# EDC-1.net
KiCad netlist of a schematic drawn in EAGLE
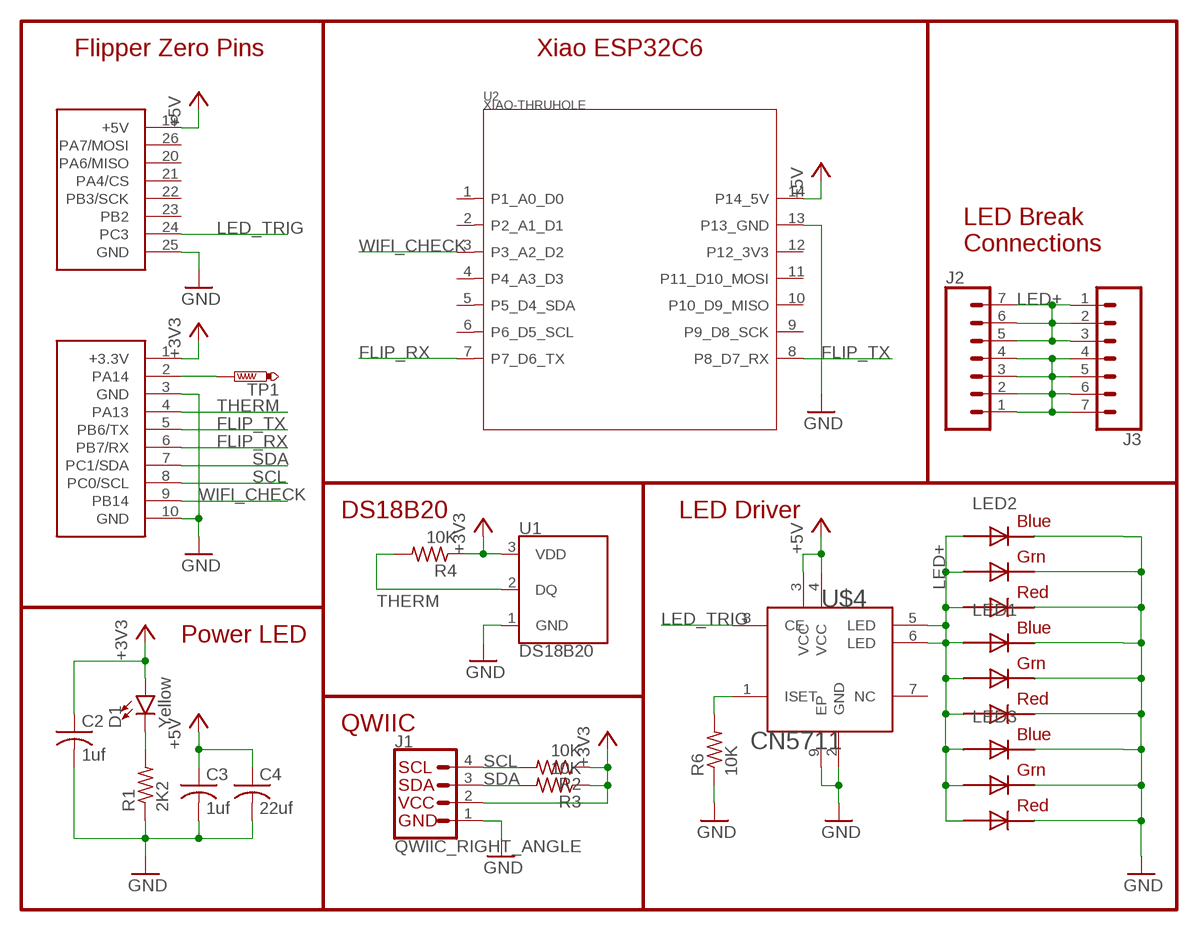
[diagram p0: schematic, sheet 1]

(export (version "E")
  (design (tool "Eeschema 10.0.6"))
  (components
    (comp (ref "C2")
      (value "1uf")
      (footprint "eagle-import:C0805")
      (libsource (lib "eagle-import") (part "C-USC0805"))
    )
    (comp (ref "C3")
      (value "1uf")
      (footprint "eagle-import:C0805")
      (libsource (lib "eagle-import") (part "C-USC0805"))
    )
    (comp (ref "C4")
      (value "22uf")
      (footprint "eagle-import:C3216")
      (libsource (lib "eagle-import") (part "C-USC3216"))
    )
    (comp (ref "D1")
      (value "Yellow")
      (footprint "eagle-import:LED-1206")
      (libsource (lib "eagle-import") (part "LED-YELLOWLILYPAD"))
    )
    (comp (ref "J1")
      (value "QWIIC_RIGHT_ANGLE")
      (footprint "eagle-import:JST04_1MM_RA")
      (libsource (lib "eagle-import") (part "QWIIC_CONNECTORJS-1MM"))
    )
    (comp (ref "J2")
      (value "CONN_07LONGPADS")
      (footprint "eagle-import:1X07_LONGPADS")
      (libsource (lib "eagle-import") (part "CONN_07LONGPADS"))
    )
    (comp (ref "J3")
      (value "CONN_07LONGPADS")
      (footprint "eagle-import:1X07_LONGPADS")
      (libsource (lib "eagle-import") (part "CONN_07LONGPADS"))
    )
    (comp (ref "LED1")
      (value "RGBLED5050")
      (footprint "eagle-import:RGBLED5050")
      (libsource (lib "eagle-import") (part "RGBLED5050"))
    )
    (comp (ref "LED2")
      (value "RGBLED5050")
      (footprint "eagle-import:RGBLED5050")
      (libsource (lib "eagle-import") (part "RGBLED5050"))
    )
    (comp (ref "LED3")
      (value "RGBLED5050")
      (footprint "eagle-import:RGBLED5050")
      (libsource (lib "eagle-import") (part "RGBLED5050"))
    )
    (comp (ref "R1")
      (value "2K2")
      (footprint "eagle-import:R0805")
      (libsource (lib "eagle-import") (part "R-US_R0805"))
    )
    (comp (ref "R2")
      (value "10K")
      (footprint "eagle-import:R0805")
      (libsource (lib "eagle-import") (part "R-US_R0805"))
    )
    (comp (ref "R3")
      (value "10K")
      (footprint "eagle-import:R0805")
      (libsource (lib "eagle-import") (part "R-US_R0805"))
    )
    (comp (ref "R4")
      (value "10K")
      (footprint "eagle-import:R0805")
      (libsource (lib "eagle-import") (part "R-US_R0805"))
    )
    (comp (ref "R6")
      (value "10K")
      (footprint "eagle-import:R0805")
      (libsource (lib "eagle-import") (part "R-US_R0805"))
    )
    (comp (ref "TP1")
      (value "PTR1PAD1-13")
      (footprint "eagle-import:P1-13")
      (libsource (lib "eagle-import") (part "PTR1PAD1-13"))
    )
    (comp (ref "U$1")
      (value "BOTH-SMD")
      (footprint "eagle-import:BOTH-SMD")
      (libsource (lib "eagle-import") (part "BOTH-SMD"))
    )
    (comp (ref "U$4")
      (value "CN5711")
      (footprint "eagle-import:SOIC127P600X175-9N")
      (libsource (lib "eagle-import") (part "CN5711"))
    )
    (comp (ref "U1")
      (value "DS18B20")
      (footprint "eagle-import:TO-92-AMMO")
      (fields (field (name "MF") "UMW"))
      (libsource (lib "eagle-import") (part "DS18B20"))
    )
    (comp (ref "U2")
      (value "XIAO-THRUHOLE")
      (footprint "eagle-import:XIAO-GENERIC-THRUHOLE-MODULE14P-2.54-21X17.8MM")
      (libsource (lib "eagle-import") (part "XIAO-THRUHOLE"))
    )
  )
  (nets
    (net (code "1") (name "+3V3") (class "Default")
      (node (ref "C2") (pin "1") (pinfunction "1_1") (pintype "passive"))
      (node (ref "D1") (pin "A") (pinfunction "A_A") (pintype "passive"))
      (node (ref "J1") (pin "2") (pinfunction "2_2") (pintype "power_in"))
      (node (ref "R2") (pin "1") (pinfunction "1_1") (pintype "passive"))
      (node (ref "R3") (pin "1") (pinfunction "1_1") (pintype "passive"))
      (node (ref "R4") (pin "1") (pinfunction "1_1") (pintype "passive"))
      (node (ref "U$1") (pin "1") (pinfunction "+3.3V_1") (pintype "bidirectional"))
      (node (ref "U1") (pin "3") (pinfunction "VDD_3") (pintype "power_in"))
    )
    (net (code "2") (name "+5V") (class "Default")
      (node (ref "C3") (pin "1") (pinfunction "1_1") (pintype "passive"))
      (node (ref "C4") (pin "1") (pinfunction "1_1") (pintype "passive"))
      (node (ref "U$1") (pin "19") (pinfunction "+5V_19") (pintype "bidirectional"))
      (node (ref "U$4") (pin "3") (pinfunction "VCC_3") (pintype "bidirectional"))
      (node (ref "U$4") (pin "4") (pinfunction "VCC_4") (pintype "bidirectional"))
      (node (ref "U2") (pin "14") (pinfunction "P14_5V_14") (pintype "bidirectional"))
    )
    (net (code "3") (name "/FLIP_RX") (class "Default")
      (node (ref "U$1") (pin "6") (pinfunction "PB7/RX_6") (pintype "bidirectional"))
      (node (ref "U2") (pin "7") (pinfunction "P7_D6_TX_7") (pintype "bidirectional"))
    )
    (net (code "4") (name "/FLIP_TX") (class "Default")
      (node (ref "U$1") (pin "5") (pinfunction "PB6/TX_5") (pintype "bidirectional"))
      (node (ref "U2") (pin "8") (pinfunction "P8_D7_RX_8") (pintype "bidirectional"))
    )
    (net (code "5") (name "/LED+") (class "Default")
      (node (ref "J2") (pin "5") (pinfunction "5_5") (pintype "passive"))
      (node (ref "J2") (pin "6") (pinfunction "6_6") (pintype "passive"))
      (node (ref "J2") (pin "7") (pinfunction "7_7") (pintype "passive"))
      (node (ref "J3") (pin "1") (pinfunction "1_1") (pintype "passive"))
      (node (ref "J3") (pin "2") (pinfunction "2_2") (pintype "passive"))
      (node (ref "J3") (pin "3") (pinfunction "3_3") (pintype "passive"))
      (node (ref "LED1") (pin "1") (pinfunction "GREEN_A_1") (pintype "bidirectional"))
      (node (ref "LED1") (pin "2") (pinfunction "RED_A_2") (pintype "bidirectional"))
      (node (ref "LED1") (pin "3") (pinfunction "BLUE_A_3") (pintype "bidirectional"))
      (node (ref "LED2") (pin "1") (pinfunction "GREEN_A_1") (pintype "bidirectional"))
      (node (ref "LED2") (pin "2") (pinfunction "RED_A_2") (pintype "bidirectional"))
      (node (ref "LED2") (pin "3") (pinfunction "BLUE_A_3") (pintype "bidirectional"))
      (node (ref "LED3") (pin "1") (pinfunction "GREEN_A_1") (pintype "bidirectional"))
      (node (ref "LED3") (pin "2") (pinfunction "RED_A_2") (pintype "bidirectional"))
      (node (ref "LED3") (pin "3") (pinfunction "BLUE_A_3") (pintype "bidirectional"))
      (node (ref "U$4") (pin "5") (pinfunction "LED_5") (pintype "bidirectional"))
      (node (ref "U$4") (pin "6") (pinfunction "LED_6") (pintype "bidirectional"))
    )
    (net (code "6") (name "/LED_TRIG") (class "Default")
      (node (ref "U$1") (pin "24") (pinfunction "PC3_24") (pintype "bidirectional"))
      (node (ref "U$4") (pin "8") (pinfunction "CE_8") (pintype "bidirectional"))
    )
    (net (code "7") (name "/SCL") (class "Default")
      (node (ref "J1") (pin "4") (pinfunction "4_4") (pintype "passive"))
      (node (ref "R2") (pin "2") (pinfunction "2_2") (pintype "passive"))
      (node (ref "U$1") (pin "8") (pinfunction "PC0/SCL_8") (pintype "bidirectional"))
    )
    (net (code "8") (name "/SDA") (class "Default")
      (node (ref "J1") (pin "3") (pinfunction "3_3") (pintype "passive"))
      (node (ref "R3") (pin "2") (pinfunction "2_2") (pintype "passive"))
      (node (ref "U$1") (pin "7") (pinfunction "PC1/SDA_7") (pintype "bidirectional"))
    )
    (net (code "9") (name "/THERM") (class "Default")
      (node (ref "R4") (pin "2") (pinfunction "2_2") (pintype "passive"))
      (node (ref "U$1") (pin "4") (pinfunction "PA13_4") (pintype "bidirectional"))
      (node (ref "U1") (pin "2") (pinfunction "DQ_2") (pintype "bidirectional"))
    )
    (net (code "10") (name "/WIFI_CHECK") (class "Default")
      (node (ref "U$1") (pin "9") (pinfunction "PB14_9") (pintype "bidirectional"))
      (node (ref "U2") (pin "3") (pinfunction "P3_A2_D2_3") (pintype "bidirectional"))
    )
    (net (code "11") (name "GND") (class "Default")
      (node (ref "C2") (pin "2") (pinfunction "2_2") (pintype "passive"))
      (node (ref "C3") (pin "2") (pinfunction "2_2") (pintype "passive"))
      (node (ref "C4") (pin "2") (pinfunction "2_2") (pintype "passive"))
      (node (ref "J1") (pin "1") (pinfunction "1_1") (pintype "power_in"))
      (node (ref "J2") (pin "1") (pinfunction "1_1") (pintype "passive"))
      (node (ref "J2") (pin "2") (pinfunction "2_2") (pintype "passive"))
      (node (ref "J2") (pin "3") (pinfunction "3_3") (pintype "passive"))
      (node (ref "J2") (pin "4") (pinfunction "4_4") (pintype "passive"))
      (node (ref "J3") (pin "4") (pinfunction "4_4") (pintype "passive"))
      (node (ref "J3") (pin "5") (pinfunction "5_5") (pintype "passive"))
      (node (ref "J3") (pin "6") (pinfunction "6_6") (pintype "passive"))
      (node (ref "J3") (pin "7") (pinfunction "7_7") (pintype "passive"))
      (node (ref "LED1") (pin "4") (pinfunction "BLUE_C_4") (pintype "bidirectional"))
      (node (ref "LED1") (pin "5") (pinfunction "RED_C_5") (pintype "bidirectional"))
      (node (ref "LED1") (pin "6") (pinfunction "GREEN_C_6") (pintype "bidirectional"))
      (node (ref "LED2") (pin "4") (pinfunction "BLUE_C_4") (pintype "bidirectional"))
      (node (ref "LED2") (pin "5") (pinfunction "RED_C_5") (pintype "bidirectional"))
      (node (ref "LED2") (pin "6") (pinfunction "GREEN_C_6") (pintype "bidirectional"))
      (node (ref "LED3") (pin "4") (pinfunction "BLUE_C_4") (pintype "bidirectional"))
      (node (ref "LED3") (pin "5") (pinfunction "RED_C_5") (pintype "bidirectional"))
      (node (ref "LED3") (pin "6") (pinfunction "GREEN_C_6") (pintype "bidirectional"))
      (node (ref "R1") (pin "1") (pinfunction "1_1") (pintype "passive"))
      (node (ref "R6") (pin "1") (pinfunction "1_1") (pintype "passive"))
      (node (ref "U$1") (pin "10") (pinfunction "GND_10") (pintype "bidirectional"))
      (node (ref "U$1") (pin "25") (pinfunction "GND_25") (pintype "bidirectional"))
      (node (ref "U$1") (pin "3") (pinfunction "GND_3") (pintype "bidirectional"))
      (node (ref "U$4") (pin "2") (pinfunction "GND_2") (pintype "bidirectional"))
      (node (ref "U$4") (pin "9") (pinfunction "EP_9") (pintype "bidirectional"))
      (node (ref "U1") (pin "1") (pinfunction "GND_1") (pintype "power_in"))
      (node (ref "U2") (pin "13") (pinfunction "P13_GND_13") (pintype "bidirectional"))
    )
    (net (code "12") (name "Net-(D1-PadC)") (class "Default")
      (node (ref "D1") (pin "C") (pinfunction "C_C") (pintype "passive"))
      (node (ref "R1") (pin "2") (pinfunction "2_2") (pintype "passive"))
    )
    (net (code "13") (name "Net-(U$1B-PA14)") (class "Default")
      (node (ref "TP1") (pin "TP") (pinfunction "TP_TP") (pintype "input"))
      (node (ref "U$1") (pin "2") (pinfunction "PA14_2") (pintype "bidirectional"))
    )
    (net (code "14") (name "Net-(U$4-ISET)") (class "Default")
      (node (ref "R6") (pin "2") (pinfunction "2_2") (pintype "passive"))
      (node (ref "U$4") (pin "1") (pinfunction "ISET_1") (pintype "bidirectional"))
    )
    (net (code "15") (name "unconnected-(U$1A-PA4{slash}CS-Pad21)") (class "Default")
      (node (ref "U$1") (pin "21") (pinfunction "PA4/CS_21") (pintype "bidirectional"))
    )
    (net (code "16") (name "unconnected-(U$1A-PA6{slash}MISO-Pad20)") (class "Default")
      (node (ref "U$1") (pin "20") (pinfunction "PA6/MISO_20") (pintype "bidirectional"))
    )
    (net (code "17") (name "unconnected-(U$1A-PA7{slash}MOSI-Pad26)") (class "Default")
      (node (ref "U$1") (pin "26") (pinfunction "PA7/MOSI_26") (pintype "bidirectional"))
    )
    (net (code "18") (name "unconnected-(U$1A-PB2-Pad23)") (class "Default")
      (node (ref "U$1") (pin "23") (pinfunction "PB2_23") (pintype "bidirectional"))
    )
    (net (code "19") (name "unconnected-(U$1A-PB3{slash}SCK-Pad22)") (class "Default")
      (node (ref "U$1") (pin "22") (pinfunction "PB3/SCK_22") (pintype "bidirectional"))
    )
    (net (code "20") (name "unconnected-(U$4-NC-Pad7)") (class "Default")
      (node (ref "U$4") (pin "7") (pinfunction "NC_7") (pintype "bidirectional"))
    )
    (net (code "21") (name "unconnected-(U2-P1_A0_D0-Pad1)") (class "Default")
      (node (ref "U2") (pin "1") (pinfunction "P1_A0_D0_1") (pintype "bidirectional"))
    )
    (net (code "22") (name "unconnected-(U2-P2_A1_D1-Pad2)") (class "Default")
      (node (ref "U2") (pin "2") (pinfunction "P2_A1_D1_2") (pintype "bidirectional"))
    )
    (net (code "23") (name "unconnected-(U2-P4_A3_D3-Pad4)") (class "Default")
      (node (ref "U2") (pin "4") (pinfunction "P4_A3_D3_4") (pintype "bidirectional"))
    )
    (net (code "24") (name "unconnected-(U2-P5_D4_SDA-Pad5)") (class "Default")
      (node (ref "U2") (pin "5") (pinfunction "P5_D4_SDA_5") (pintype "bidirectional"))
    )
    (net (code "25") (name "unconnected-(U2-P6_D5_SCL-Pad6)") (class "Default")
      (node (ref "U2") (pin "6") (pinfunction "P6_D5_SCL_6") (pintype "bidirectional"))
    )
    (net (code "26") (name "unconnected-(U2-P9_D8_SCK-Pad9)") (class "Default")
      (node (ref "U2") (pin "9") (pinfunction "P9_D8_SCK_9") (pintype "bidirectional"))
    )
    (net (code "27") (name "unconnected-(U2-P10_D9_MISO-Pad10)") (class "Default")
      (node (ref "U2") (pin "10") (pinfunction "P10_D9_MISO_10") (pintype "bidirectional"))
    )
    (net (code "28") (name "unconnected-(U2-P11_D10_MOSI-Pad11)") (class "Default")
      (node (ref "U2") (pin "11") (pinfunction "P11_D10_MOSI_11") (pintype "bidirectional"))
    )
    (net (code "29") (name "unconnected-(U2-P12_3V3-Pad12)") (class "Default")
      (node (ref "U2") (pin "12") (pinfunction "P12_3V3_12") (pintype "bidirectional"))
    )
  )
)
